# ESP8266-Bootloader-01.net
KiCad netlist of a schematic drawn in EAGLE
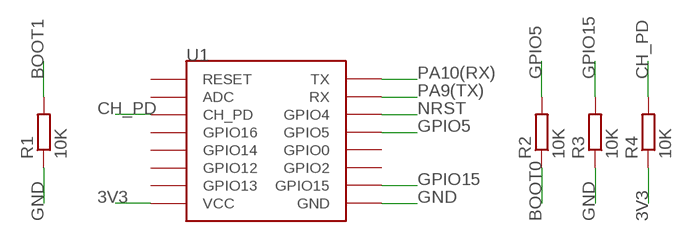
[diagram p0: schematic, sheet 1]

(export (version "E")
  (design (tool "Eeschema 10.0.6"))
  (components
    (comp (ref "R1")
      (value "10K")
      (footprint "eagle-import:R0603")
      (libsource (lib "eagle-import") (part "R-EU_R0603"))
    )
    (comp (ref "R2")
      (value "10K")
      (footprint "eagle-import:R0603")
      (libsource (lib "eagle-import") (part "R-EU_R0603"))
    )
    (comp (ref "R3")
      (value "10K")
      (footprint "eagle-import:R0603")
      (libsource (lib "eagle-import") (part "R-EU_R0603"))
    )
    (comp (ref "R4")
      (value "10K")
      (footprint "eagle-import:R0603")
      (libsource (lib "eagle-import") (part "R-EU_R0603"))
    )
    (comp (ref "U1")
      (value "ESP12")
      (footprint "eagle-import:ESP12")
      (libsource (lib "eagle-import") (part "ESP12"))
    )
  )
  (nets
    (net (code "1") (name "/3V3") (class "Default")
      (node (ref "R4") (pin "1") (pinfunction "1_1") (pintype "passive"))
      (node (ref "U1") (pin "VCC") (pinfunction "VCC_VCC") (pintype "bidirectional"))
    )
    (net (code "2") (name "/BOOT0") (class "Default")
      (node (ref "R2") (pin "1") (pinfunction "1_1") (pintype "passive"))
    )
    (net (code "3") (name "/BOOT1") (class "Default")
      (node (ref "R1") (pin "2") (pinfunction "2_2") (pintype "passive"))
    )
    (net (code "4") (name "/CH_PD") (class "Default")
      (node (ref "R4") (pin "2") (pinfunction "2_2") (pintype "passive"))
      (node (ref "U1") (pin "CH_PD") (pinfunction "CH_PD_CH_PD") (pintype "bidirectional"))
    )
    (net (code "5") (name "/GND") (class "Default")
      (node (ref "R1") (pin "1") (pinfunction "1_1") (pintype "passive"))
      (node (ref "R3") (pin "1") (pinfunction "1_1") (pintype "passive"))
      (node (ref "U1") (pin "GND") (pinfunction "GND_GND") (pintype "bidirectional"))
    )
    (net (code "6") (name "/GPIO5") (class "Default")
      (node (ref "R2") (pin "2") (pinfunction "2_2") (pintype "passive"))
      (node (ref "U1") (pin "GPIO5") (pinfunction "GPIO5_GPIO5") (pintype "bidirectional"))
    )
    (net (code "7") (name "/GPIO15") (class "Default")
      (node (ref "R3") (pin "2") (pinfunction "2_2") (pintype "passive"))
      (node (ref "U1") (pin "GPIO15") (pinfunction "GPIO15_GPIO15") (pintype "bidirectional"))
    )
    (net (code "8") (name "/NRST") (class "Default")
      (node (ref "U1") (pin "GPIO4") (pinfunction "GPIO4_GPIO4") (pintype "bidirectional"))
    )
    (net (code "9") (name "/PA9(TX)") (class "Default")
      (node (ref "U1") (pin "RX") (pinfunction "RX_RX") (pintype "bidirectional"))
    )
    (net (code "10") (name "/PA10(RX)") (class "Default")
      (node (ref "U1") (pin "TX") (pinfunction "TX_TX") (pintype "bidirectional"))
    )
    (net (code "11") (name "unconnected-(U1-PadADC)") (class "Default")
      (node (ref "U1") (pin "ADC") (pinfunction "ADC_ADC") (pintype "bidirectional"))
    )
    (net (code "12") (name "unconnected-(U1-PadGPIO0)") (class "Default")
      (node (ref "U1") (pin "GPIO0") (pinfunction "GPIO0_GPIO0") (pintype "bidirectional"))
    )
    (net (code "13") (name "unconnected-(U1-PadGPIO2)") (class "Default")
      (node (ref "U1") (pin "GPIO2") (pinfunction "GPIO2_GPIO2") (pintype "bidirectional"))
    )
    (net (code "14") (name "unconnected-(U1-PadGPIO12)") (class "Default")
      (node (ref "U1") (pin "GPIO12") (pinfunction "GPIO12_GPIO12") (pintype "bidirectional"))
    )
    (net (code "15") (name "unconnected-(U1-PadGPIO13)") (class "Default")
      (node (ref "U1") (pin "GPIO13") (pinfunction "GPIO13_GPIO13") (pintype "bidirectional"))
    )
    (net (code "16") (name "unconnected-(U1-PadGPIO14)") (class "Default")
      (node (ref "U1") (pin "GPIO14") (pinfunction "GPIO14_GPIO14") (pintype "bidirectional"))
    )
    (net (code "17") (name "unconnected-(U1-PadGPIO16)") (class "Default")
      (node (ref "U1") (pin "GPIO16") (pinfunction "GPIO16_GPIO16") (pintype "bidirectional"))
    )
    (net (code "18") (name "unconnected-(U1-PadRESET)") (class "Default")
      (node (ref "U1") (pin "RESET") (pinfunction "RESET_RESET") (pintype "bidirectional"))
    )
  )
)
